# VL6180_Breakout.net
KiCad netlist of a schematic drawn in EAGLE
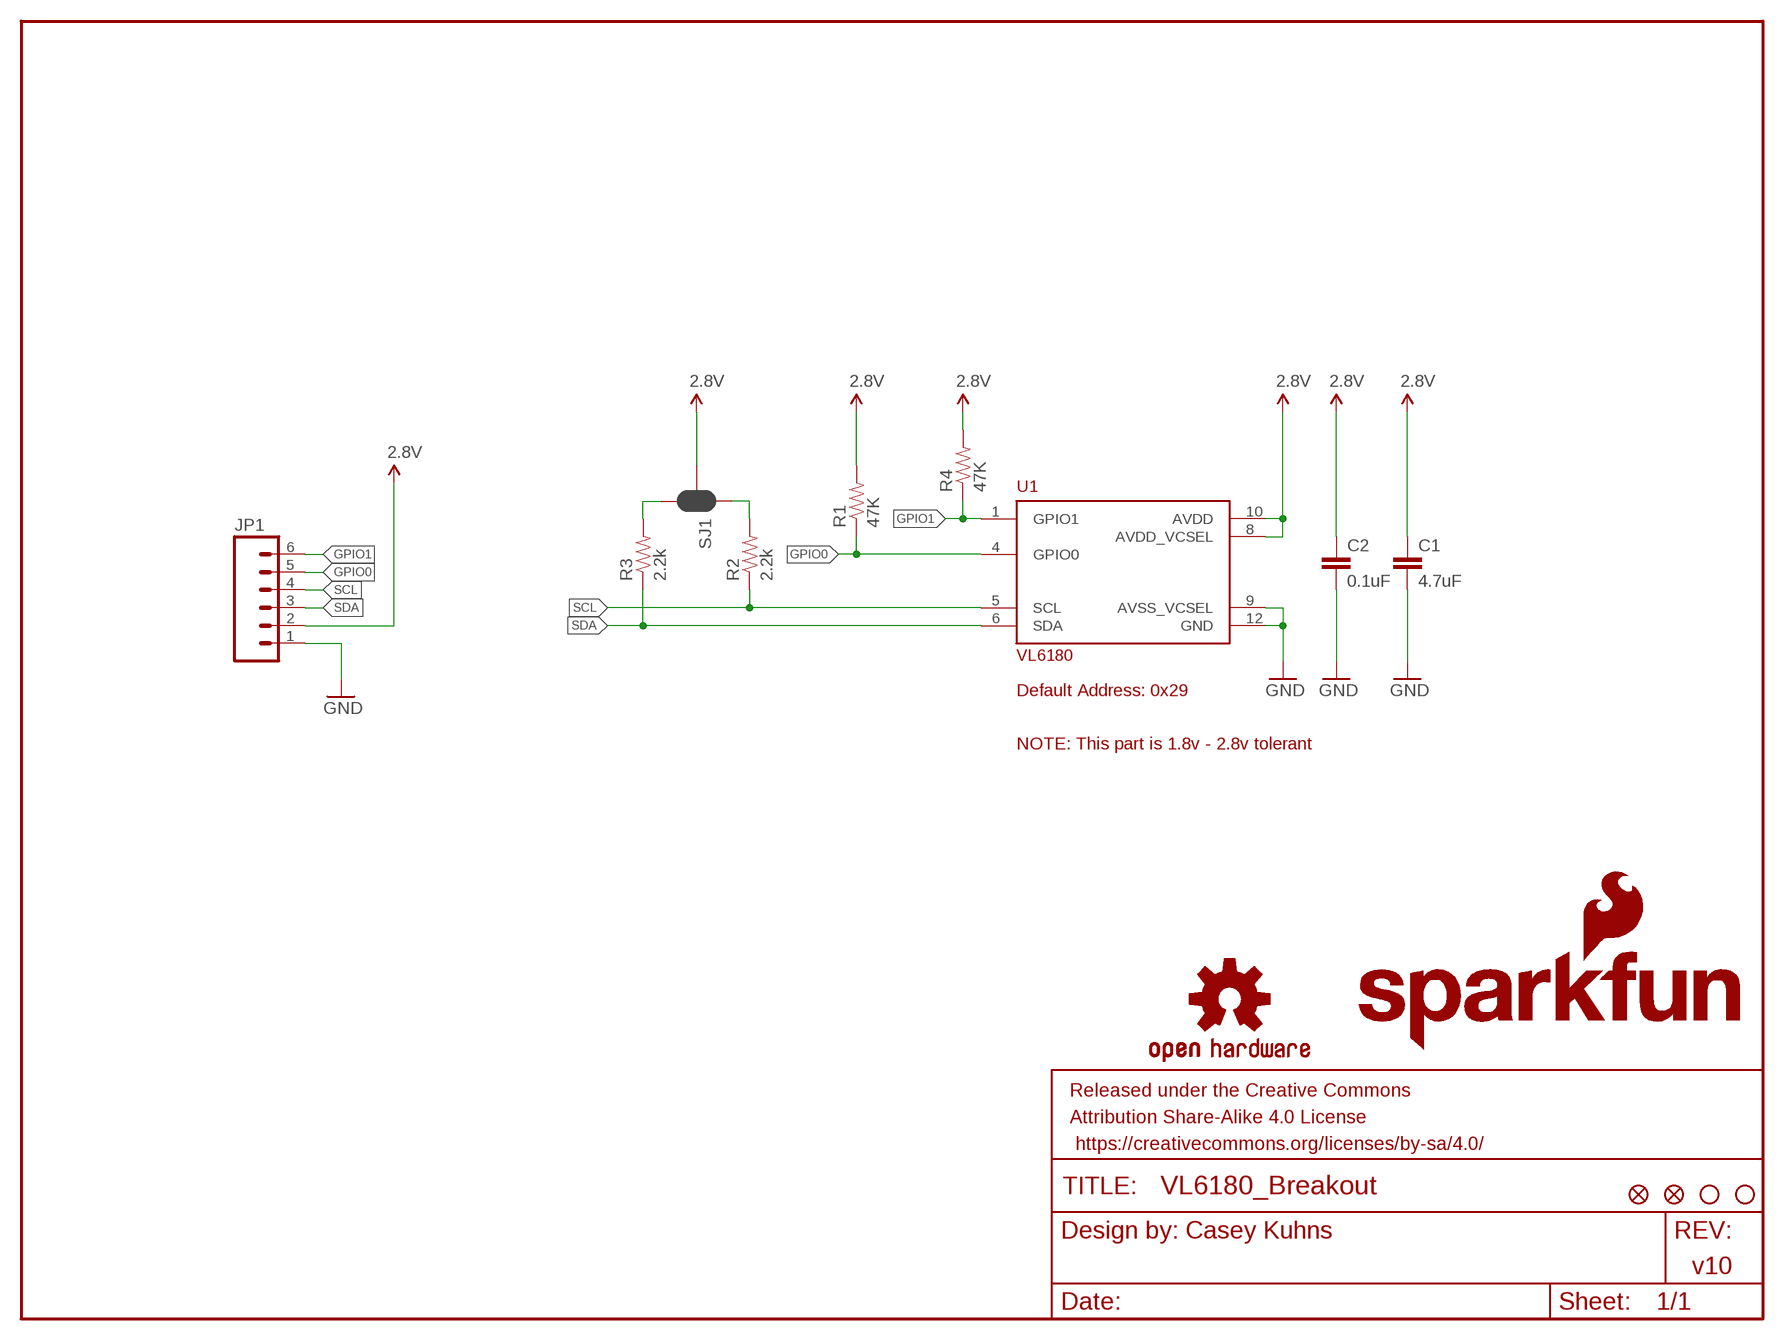
[diagram p0: schematic, sheet 1]

(export (version "E")
  (design (tool "Eeschema 10.0.6"))
  (components
    (comp (ref "C1")
      (value "4.7uF")
      (footprint "eagle-import:0603-CAP")
      (libsource (lib "eagle-import") (part "4.7UF-6.3V-10%(0603)0603"))
    )
    (comp (ref "C2")
      (value "0.1uF")
      (footprint "eagle-import:0603-CAP")
      (libsource (lib "eagle-import") (part "0.1UF-25V(+80/-20%)(0603)"))
    )
    (comp (ref "FID1")
      (value "FIDUCIAL1X2")
      (footprint "eagle-import:FIDUCIAL-1X2")
      (libsource (lib "eagle-import") (part "FIDUCIAL1X2"))
    )
    (comp (ref "FID2")
      (value "FIDUCIAL1X2")
      (footprint "eagle-import:FIDUCIAL-1X2")
      (libsource (lib "eagle-import") (part "FIDUCIAL1X2"))
    )
    (comp (ref "FRAME1")
      (value "FRAME-LETTER")
      (footprint "eagle-import:CREATIVE_COMMONS")
      (libsource (lib "eagle-import") (part "FRAME-LETTER"))
    )
    (comp (ref "JP1")
      (value "M06SIP")
      (footprint "eagle-import:1X06")
      (libsource (lib "eagle-import") (part "M06SIP"))
    )
    (comp (ref "LOGO1")
      (value "SFE_LOGO_NAME_FLAME.1_INCH")
      (footprint "eagle-import:SFE_LOGO_NAME_FLAME_.1")
      (libsource (lib "eagle-import") (part "SFE_LOGO_NAME_FLAME.1_INCH"))
    )
    (comp (ref "LOGO2")
      (value "OSHW-LOGOS")
      (footprint "eagle-import:OSHW-LOGO-S")
      (libsource (lib "eagle-import") (part "OSHW-LOGOS"))
    )
    (comp (ref "R1")
      (value "47K")
      (footprint "eagle-import:0603-RES")
      (libsource (lib "eagle-import") (part "47KOHM1/10W1%(0603)"))
    )
    (comp (ref "R2")
      (value "2.2k")
      (footprint "eagle-import:0603-RES")
      (libsource (lib "eagle-import") (part "2.2KOHM1/10W1%(0603)"))
    )
    (comp (ref "R3")
      (value "2.2k")
      (footprint "eagle-import:0603-RES")
      (libsource (lib "eagle-import") (part "2.2KOHM1/10W1%(0603)"))
    )
    (comp (ref "R4")
      (value "47K")
      (footprint "eagle-import:0603-RES")
      (libsource (lib "eagle-import") (part "47KOHM1/10W1%(0603)"))
    )
    (comp (ref "SJ1")
      (value "JUMPER-PAD-3-NC_BY_PASTE")
      (footprint "eagle-import:PAD-JUMPER-3-NC_BY_PASTE_YES_SILK_FULL_BOX")
      (libsource (lib "eagle-import") (part "JUMPER-PAD-3-NC_BY_PASTE"))
    )
    (comp (ref "STANDOFF1")
      (value "STAND-OFF")
      (footprint "eagle-import:STAND-OFF")
      (libsource (lib "eagle-import") (part "STAND-OFF"))
    )
    (comp (ref "STANDOFF2")
      (value "STAND-OFF")
      (footprint "eagle-import:STAND-OFF")
      (libsource (lib "eagle-import") (part "STAND-OFF"))
    )
    (comp (ref "U1")
      (value "VL6180")
      (footprint "eagle-import:VL6180")
      (libsource (lib "eagle-import") (part "VL6180"))
    )
  )
  (nets
    (net (code "1") (name "2.8V") (class "Default")
      (node (ref "C1") (pin "1") (pinfunction "1_1") (pintype "passive"))
      (node (ref "C2") (pin "1") (pinfunction "1_1") (pintype "passive"))
      (node (ref "JP1") (pin "2") (pinfunction "2_2") (pintype "passive"))
      (node (ref "R1") (pin "2") (pinfunction "2_2") (pintype "passive"))
      (node (ref "R4") (pin "2") (pinfunction "2_2") (pintype "passive"))
      (node (ref "SJ1") (pin "2") (pinfunction "2_2") (pintype "passive"))
      (node (ref "U1") (pin "10") (pinfunction "AVDD_10") (pintype "bidirectional"))
      (node (ref "U1") (pin "8") (pinfunction "AVDD_VCSEL_8") (pintype "bidirectional"))
    )
    (net (code "2") (name "GND") (class "Default")
      (node (ref "C1") (pin "2") (pinfunction "2_2") (pintype "passive"))
      (node (ref "C2") (pin "2") (pinfunction "2_2") (pintype "passive"))
      (node (ref "JP1") (pin "1") (pinfunction "1_1") (pintype "passive"))
      (node (ref "U1") (pin "12") (pinfunction "GND_12") (pintype "bidirectional"))
      (node (ref "U1") (pin "9") (pinfunction "AVSS_VCSEL_9") (pintype "bidirectional"))
    )
    (net (code "3") (name "GPIO0") (class "Default")
      (node (ref "JP1") (pin "5") (pinfunction "5_5") (pintype "passive"))
      (node (ref "R1") (pin "1") (pinfunction "1_1") (pintype "passive"))
      (node (ref "U1") (pin "4") (pinfunction "GPIO0_4") (pintype "bidirectional"))
    )
    (net (code "4") (name "GPIO1") (class "Default")
      (node (ref "JP1") (pin "6") (pinfunction "6_6") (pintype "passive"))
      (node (ref "R4") (pin "1") (pinfunction "1_1") (pintype "passive"))
      (node (ref "U1") (pin "1") (pinfunction "GPIO1_1") (pintype "bidirectional"))
    )
    (net (code "5") (name "Net-(R2-Pad2)") (class "Default")
      (node (ref "R2") (pin "2") (pinfunction "2_2") (pintype "passive"))
      (node (ref "SJ1") (pin "1") (pinfunction "1_1") (pintype "passive"))
    )
    (net (code "6") (name "Net-(R3-Pad2)") (class "Default")
      (node (ref "R3") (pin "2") (pinfunction "2_2") (pintype "passive"))
      (node (ref "SJ1") (pin "3") (pinfunction "3_3") (pintype "passive"))
    )
    (net (code "7") (name "SCL") (class "Default")
      (node (ref "JP1") (pin "4") (pinfunction "4_4") (pintype "passive"))
      (node (ref "R2") (pin "1") (pinfunction "1_1") (pintype "passive"))
      (node (ref "U1") (pin "5") (pinfunction "SCL_5") (pintype "bidirectional"))
    )
    (net (code "8") (name "SDA") (class "Default")
      (node (ref "JP1") (pin "3") (pinfunction "3_3") (pintype "passive"))
      (node (ref "R3") (pin "1") (pinfunction "1_1") (pintype "passive"))
      (node (ref "U1") (pin "6") (pinfunction "SDA_6") (pintype "bidirectional"))
    )
  )
)
